# RT_SUPER_EXT2.net
KiCad netlist of a schematic drawn in Altium Designer
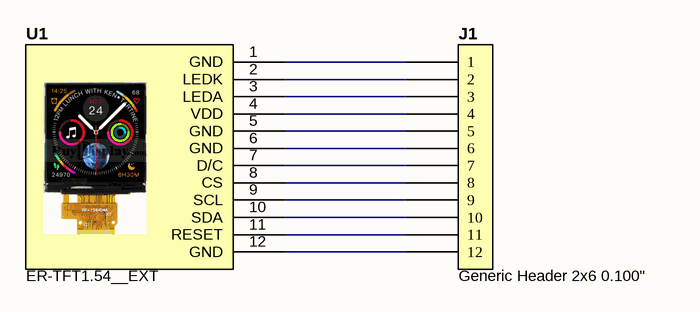
[diagram p0: RT_SUPER_EXT2.SchDoc]

(export (version "E")
  (design (tool "Eeschema 10.0.6"))
  (components
    (comp (ref "J1")
      (value "Generic Header 2x6 0.100\"")
      (footprint "HEADER 2x6 .100\"")
      (libsource (lib "eConnector_Header") (part "HEADER_12"))
    )
    (comp (ref "U1")
      (value "ER-TFT1.54__EXT")
      (footprint "ER-TFT1.54-1 - EXT")
      (description "EXTENTION FOOTPRINT")
      (fields
        (field (name "MANUFACTURER") "Buy Display")
        (field (name "MANUFACTURER PART NUMBER") "ER-TFT1.54-1")
      )
      (libsource (lib "eDisplay") (part "ER-TFT1.54__EXT"))
    )
  )
  (nets
    (net (code "1") (name "Net-(J1-Pad1)") (class "Default")
      (node (ref "J1") (pin "1") (pinfunction "1_1") (pintype "passive"))
      (node (ref "U1") (pin "1") (pinfunction "GND_1") (pintype "passive"))
    )
    (net (code "2") (name "Net-(J1-Pad5)") (class "Default")
      (node (ref "J1") (pin "5") (pinfunction "5_5") (pintype "passive"))
      (node (ref "U1") (pin "5") (pinfunction "GND_5") (pintype "passive"))
    )
    (net (code "3") (name "Net-(J1-Pad6)") (class "Default")
      (node (ref "J1") (pin "6") (pinfunction "6_6") (pintype "passive"))
      (node (ref "U1") (pin "6") (pinfunction "GND_6") (pintype "passive"))
    )
    (net (code "4") (name "Net-(J1-Pad12)") (class "Default")
      (node (ref "J1") (pin "12") (pinfunction "12_12") (pintype "passive"))
      (node (ref "U1") (pin "12") (pinfunction "GND_12") (pintype "passive"))
    )
    (net (code "5") (name "Net-(U1-CS)") (class "Default")
      (node (ref "J1") (pin "8") (pinfunction "8_8") (pintype "passive"))
      (node (ref "U1") (pin "8") (pinfunction "CS_8") (pintype "passive"))
    )
    (net (code "6") (name "Net-(U1-D{slash}C)") (class "Default")
      (node (ref "J1") (pin "7") (pinfunction "7_7") (pintype "passive"))
      (node (ref "U1") (pin "7") (pinfunction "D/C_7") (pintype "passive"))
    )
    (net (code "7") (name "Net-(U1-LEDA)") (class "Default")
      (node (ref "J1") (pin "3") (pinfunction "3_3") (pintype "passive"))
      (node (ref "U1") (pin "3") (pinfunction "LEDA_3") (pintype "passive"))
    )
    (net (code "8") (name "Net-(U1-LEDK)") (class "Default")
      (node (ref "J1") (pin "2") (pinfunction "2_2") (pintype "passive"))
      (node (ref "U1") (pin "2") (pinfunction "LEDK_2") (pintype "passive"))
    )
    (net (code "9") (name "Net-(U1-RESET)") (class "Default")
      (node (ref "J1") (pin "11") (pinfunction "11_11") (pintype "passive"))
      (node (ref "U1") (pin "11") (pinfunction "RESET_11") (pintype "passive"))
    )
    (net (code "10") (name "Net-(U1-SCL)") (class "Default")
      (node (ref "J1") (pin "9") (pinfunction "9_9") (pintype "passive"))
      (node (ref "U1") (pin "9") (pinfunction "SCL_9") (pintype "passive"))
    )
    (net (code "11") (name "Net-(U1-SDA)") (class "Default")
      (node (ref "J1") (pin "10") (pinfunction "10_10") (pintype "passive"))
      (node (ref "U1") (pin "10") (pinfunction "SDA_10") (pintype "passive"))
    )
    (net (code "12") (name "Net-(U1-VDD)") (class "Default")
      (node (ref "J1") (pin "4") (pinfunction "4_4") (pintype "passive"))
      (node (ref "U1") (pin "4") (pinfunction "VDD_4") (pintype "passive"))
    )
  )
)
